# IMX6DL_POWER.net
KiCad netlist of a schematic drawn in Altium Designer
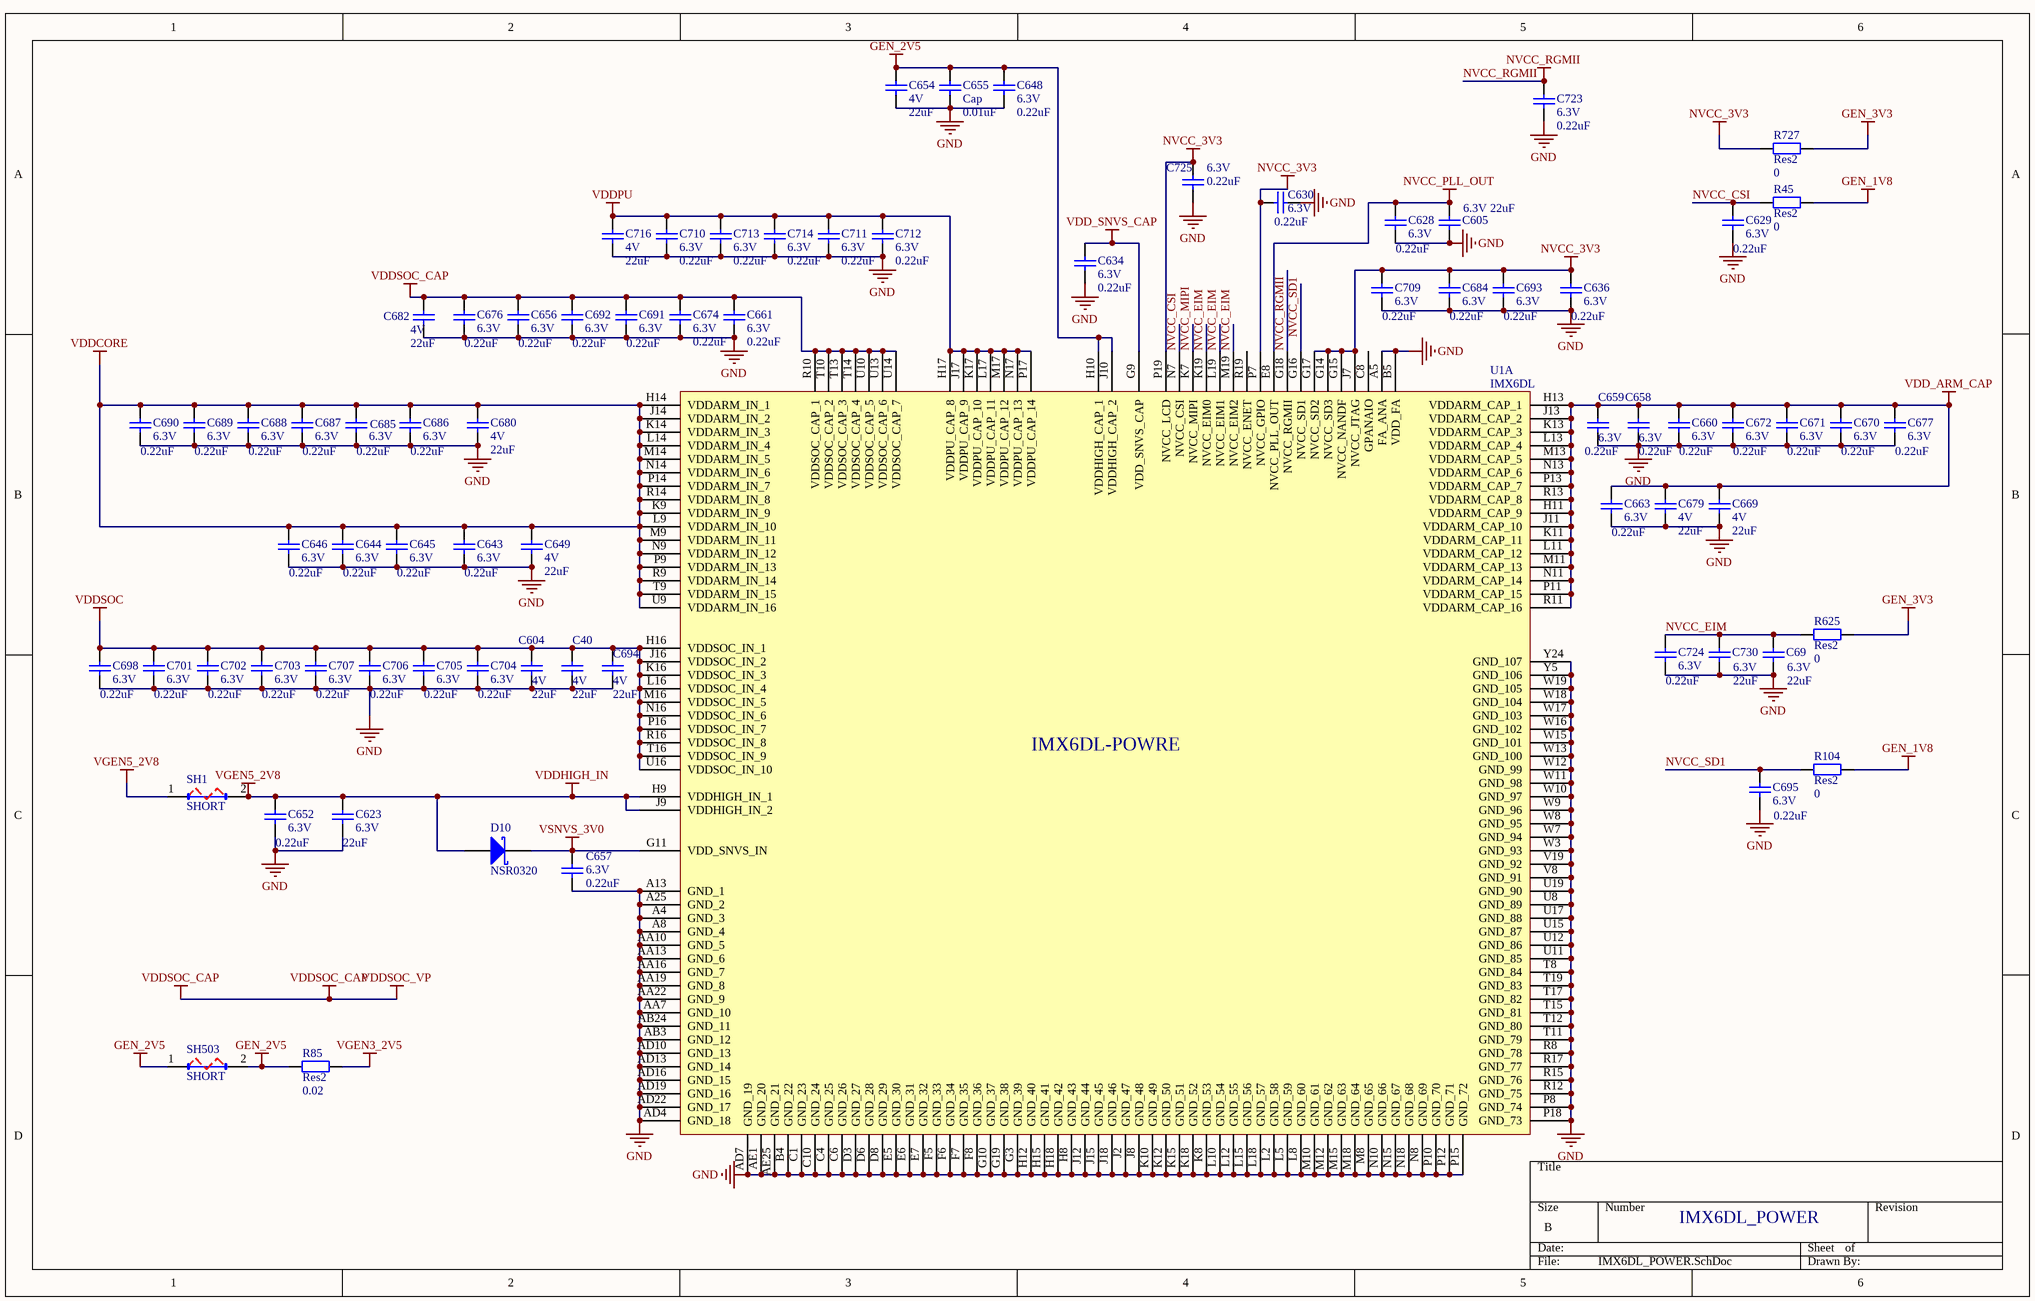
[diagram p0: IMX6DL_POWER.SchDoc]

(export (version "E")
  (design (tool "Eeschema 10.0.6"))
  (components
    (comp (ref "C40")
      (value "4V")
      (footprint "0603")
      (description "Capacitor")
      (fields (field (name "ALTIUM_VALUE") "22uF") (field (name "PUBLISHER") "Altium Limited"))
      (libsource (lib "Miscellaneous Devices") (part "Cap"))
    )
    (comp (ref "C69")
      (value "6.3V")
      (footprint "0603")
      (description "Capacitor")
      (fields (field (name "ALTIUM_VALUE") "22uF") (field (name "PUBLISHER") "Altium Limited"))
      (libsource (lib "Miscellaneous Devices") (part "Cap"))
    )
    (comp (ref "C604")
      (value "4V")
      (footprint "0603")
      (description "Capacitor")
      (fields (field (name "ALTIUM_VALUE") "22uF") (field (name "PUBLISHER") "Altium Limited"))
      (libsource (lib "Miscellaneous Devices") (part "Cap"))
    )
    (comp (ref "C605")
      (value "6.3V")
      (footprint "0603")
      (description "Capacitor")
      (fields (field (name "ALTIUM_VALUE") "22uF") (field (name "PUBLISHER") "Altium Limited"))
      (libsource (lib "Miscellaneous Devices") (part "Cap"))
    )
    (comp (ref "C623")
      (value "6.3V")
      (footprint "0603")
      (description "Capacitor")
      (fields (field (name "ALTIUM_VALUE") "22uF") (field (name "PUBLISHER") "Altium Limited"))
      (libsource (lib "Miscellaneous Devices") (part "Cap"))
    )
    (comp (ref "C628")
      (value "6.3V")
      (footprint "0201")
      (description "Capacitor")
      (fields (field (name "ALTIUM_VALUE") "0.22uF") (field (name "PUBLISHER") "Altium Limited"))
      (libsource (lib "Miscellaneous Devices") (part "Cap"))
    )
    (comp (ref "C629")
      (value "6.3V")
      (footprint "0201")
      (description "Capacitor")
      (fields (field (name "ALTIUM_VALUE") "0.22uF") (field (name "PUBLISHER") "Altium Limited"))
      (libsource (lib "Miscellaneous Devices") (part "Cap"))
    )
    (comp (ref "C630")
      (value "6.3V")
      (footprint "0201")
      (description "Capacitor")
      (fields (field (name "ALTIUM_VALUE") "0.22uF") (field (name "PUBLISHER") "Altium Limited"))
      (libsource (lib "Miscellaneous Devices") (part "Cap"))
    )
    (comp (ref "C634")
      (value "6.3V")
      (footprint "0201")
      (description "Capacitor")
      (fields (field (name "ALTIUM_VALUE") "0.22uF") (field (name "PUBLISHER") "Altium Limited"))
      (libsource (lib "Miscellaneous Devices") (part "Cap"))
    )
    (comp (ref "C636")
      (value "6.3V")
      (footprint "0201")
      (description "Capacitor")
      (fields (field (name "ALTIUM_VALUE") "0.22uF") (field (name "PUBLISHER") "Altium Limited"))
      (libsource (lib "Miscellaneous Devices") (part "Cap"))
    )
    (comp (ref "C643")
      (value "6.3V")
      (footprint "0201")
      (description "Capacitor")
      (fields (field (name "ALTIUM_VALUE") "0.22uF") (field (name "PUBLISHER") "Altium Limited"))
      (libsource (lib "Miscellaneous Devices") (part "Cap"))
    )
    (comp (ref "C644")
      (value "6.3V")
      (footprint "0201")
      (description "Capacitor")
      (fields (field (name "ALTIUM_VALUE") "0.22uF") (field (name "PUBLISHER") "Altium Limited"))
      (libsource (lib "Miscellaneous Devices") (part "Cap"))
    )
    (comp (ref "C645")
      (value "6.3V")
      (footprint "0201")
      (description "Capacitor")
      (fields (field (name "ALTIUM_VALUE") "0.22uF") (field (name "PUBLISHER") "Altium Limited"))
      (libsource (lib "Miscellaneous Devices") (part "Cap"))
    )
    (comp (ref "C646")
      (value "6.3V")
      (footprint "0201")
      (description "Capacitor")
      (fields (field (name "ALTIUM_VALUE") "0.22uF") (field (name "PUBLISHER") "Altium Limited"))
      (libsource (lib "Miscellaneous Devices") (part "Cap"))
    )
    (comp (ref "C648")
      (value "6.3V")
      (footprint "0201")
      (description "Capacitor")
      (fields (field (name "ALTIUM_VALUE") "0.22uF") (field (name "PUBLISHER") "Altium Limited"))
      (libsource (lib "Miscellaneous Devices") (part "Cap"))
    )
    (comp (ref "C649")
      (value "4V")
      (footprint "0603")
      (description "Capacitor")
      (fields (field (name "ALTIUM_VALUE") "22uF") (field (name "PUBLISHER") "Altium Limited"))
      (libsource (lib "Miscellaneous Devices") (part "Cap"))
    )
    (comp (ref "C652")
      (value "6.3V")
      (footprint "0201")
      (description "Capacitor")
      (fields (field (name "ALTIUM_VALUE") "0.22uF") (field (name "PUBLISHER") "Altium Limited"))
      (libsource (lib "Miscellaneous Devices") (part "Cap"))
    )
    (comp (ref "C654")
      (value "4V")
      (footprint "0603")
      (description "Capacitor")
      (fields (field (name "ALTIUM_VALUE") "22uF") (field (name "PUBLISHER") "Altium Limited"))
      (libsource (lib "Miscellaneous Devices") (part "Cap"))
    )
    (comp (ref "C655")
      (value "Cap")
      (footprint "0201")
      (description "Capacitor")
      (fields (field (name "ALTIUM_VALUE") "0.01uF") (field (name "PUBLISHER") "Altium Limited"))
      (libsource (lib "Miscellaneous Devices") (part "Cap"))
    )
    (comp (ref "C656")
      (value "6.3V")
      (footprint "0201")
      (description "Capacitor")
      (fields (field (name "ALTIUM_VALUE") "0.22uF") (field (name "PUBLISHER") "Altium Limited"))
      (libsource (lib "Miscellaneous Devices") (part "Cap"))
    )
    (comp (ref "C657")
      (value "6.3V")
      (footprint "0201")
      (description "Capacitor")
      (fields (field (name "ALTIUM_VALUE") "0.22uF") (field (name "PUBLISHER") "Altium Limited"))
      (libsource (lib "Miscellaneous Devices") (part "Cap"))
    )
    (comp (ref "C658")
      (value "6.3V")
      (footprint "0201")
      (description "Capacitor")
      (fields (field (name "ALTIUM_VALUE") "0.22uF") (field (name "PUBLISHER") "Altium Limited"))
      (libsource (lib "Miscellaneous Devices") (part "Cap"))
    )
    (comp (ref "C659")
      (value "6.3V")
      (footprint "0201")
      (description "Capacitor")
      (fields (field (name "ALTIUM_VALUE") "0.22uF") (field (name "PUBLISHER") "Altium Limited"))
      (libsource (lib "Miscellaneous Devices") (part "Cap"))
    )
    (comp (ref "C660")
      (value "6.3V")
      (footprint "0201")
      (description "Capacitor")
      (fields (field (name "ALTIUM_VALUE") "0.22uF") (field (name "PUBLISHER") "Altium Limited"))
      (libsource (lib "Miscellaneous Devices") (part "Cap"))
    )
    (comp (ref "C661")
      (value "6.3V")
      (footprint "0201")
      (description "Capacitor")
      (fields (field (name "ALTIUM_VALUE") "0.22uF") (field (name "PUBLISHER") "Altium Limited"))
      (libsource (lib "Miscellaneous Devices") (part "Cap"))
    )
    (comp (ref "C663")
      (value "6.3V")
      (footprint "0201")
      (description "Capacitor")
      (fields (field (name "ALTIUM_VALUE") "0.22uF") (field (name "PUBLISHER") "Altium Limited"))
      (libsource (lib "Miscellaneous Devices") (part "Cap"))
    )
    (comp (ref "C669")
      (value "4V")
      (footprint "0603")
      (description "Capacitor")
      (fields (field (name "ALTIUM_VALUE") "22uF") (field (name "PUBLISHER") "Altium Limited"))
      (libsource (lib "Miscellaneous Devices") (part "Cap"))
    )
    (comp (ref "C670")
      (value "6.3V")
      (footprint "0201")
      (description "Capacitor")
      (fields (field (name "ALTIUM_VALUE") "0.22uF") (field (name "PUBLISHER") "Altium Limited"))
      (libsource (lib "Miscellaneous Devices") (part "Cap"))
    )
    (comp (ref "C671")
      (value "6.3V")
      (footprint "0201")
      (description "Capacitor")
      (fields (field (name "ALTIUM_VALUE") "0.22uF") (field (name "PUBLISHER") "Altium Limited"))
      (libsource (lib "Miscellaneous Devices") (part "Cap"))
    )
    (comp (ref "C672")
      (value "6.3V")
      (footprint "0201")
      (description "Capacitor")
      (fields (field (name "ALTIUM_VALUE") "0.22uF") (field (name "PUBLISHER") "Altium Limited"))
      (libsource (lib "Miscellaneous Devices") (part "Cap"))
    )
    (comp (ref "C674")
      (value "6.3V")
      (footprint "0201")
      (description "Capacitor")
      (fields (field (name "ALTIUM_VALUE") "0.22uF") (field (name "PUBLISHER") "Altium Limited"))
      (libsource (lib "Miscellaneous Devices") (part "Cap"))
    )
    (comp (ref "C676")
      (value "6.3V")
      (footprint "0201")
      (description "Capacitor")
      (fields (field (name "ALTIUM_VALUE") "0.22uF") (field (name "PUBLISHER") "Altium Limited"))
      (libsource (lib "Miscellaneous Devices") (part "Cap"))
    )
    (comp (ref "C677")
      (value "6.3V")
      (footprint "0201")
      (description "Capacitor")
      (fields (field (name "ALTIUM_VALUE") "0.22uF") (field (name "PUBLISHER") "Altium Limited"))
      (libsource (lib "Miscellaneous Devices") (part "Cap"))
    )
    (comp (ref "C679")
      (value "4V")
      (footprint "0603")
      (description "Capacitor")
      (fields (field (name "ALTIUM_VALUE") "22uF") (field (name "PUBLISHER") "Altium Limited"))
      (libsource (lib "Miscellaneous Devices") (part "Cap"))
    )
    (comp (ref "C680")
      (value "4V")
      (footprint "0603")
      (description "Capacitor")
      (fields (field (name "ALTIUM_VALUE") "22uF") (field (name "PUBLISHER") "Altium Limited"))
      (libsource (lib "Miscellaneous Devices") (part "Cap"))
    )
    (comp (ref "C682")
      (value "4V")
      (footprint "0603")
      (description "Capacitor")
      (fields (field (name "ALTIUM_VALUE") "22uF") (field (name "PUBLISHER") "Altium Limited"))
      (libsource (lib "Miscellaneous Devices") (part "Cap"))
    )
    (comp (ref "C684")
      (value "6.3V")
      (footprint "0201")
      (description "Capacitor")
      (fields (field (name "ALTIUM_VALUE") "0.22uF") (field (name "PUBLISHER") "Altium Limited"))
      (libsource (lib "Miscellaneous Devices") (part "Cap"))
    )
    (comp (ref "C685")
      (value "6.3V")
      (footprint "0201")
      (description "Capacitor")
      (fields (field (name "ALTIUM_VALUE") "0.22uF") (field (name "PUBLISHER") "Altium Limited"))
      (libsource (lib "Miscellaneous Devices") (part "Cap"))
    )
    (comp (ref "C686")
      (value "6.3V")
      (footprint "0201")
      (description "Capacitor")
      (fields (field (name "ALTIUM_VALUE") "0.22uF") (field (name "PUBLISHER") "Altium Limited"))
      (libsource (lib "Miscellaneous Devices") (part "Cap"))
    )
    (comp (ref "C687")
      (value "6.3V")
      (footprint "0201")
      (description "Capacitor")
      (fields (field (name "ALTIUM_VALUE") "0.22uF") (field (name "PUBLISHER") "Altium Limited"))
      (libsource (lib "Miscellaneous Devices") (part "Cap"))
    )
    (comp (ref "C688")
      (value "6.3V")
      (footprint "0201")
      (description "Capacitor")
      (fields (field (name "ALTIUM_VALUE") "0.22uF") (field (name "PUBLISHER") "Altium Limited"))
      (libsource (lib "Miscellaneous Devices") (part "Cap"))
    )
    (comp (ref "C689")
      (value "6.3V")
      (footprint "0201")
      (description "Capacitor")
      (fields (field (name "ALTIUM_VALUE") "0.22uF") (field (name "PUBLISHER") "Altium Limited"))
      (libsource (lib "Miscellaneous Devices") (part "Cap"))
    )
    (comp (ref "C690")
      (value "6.3V")
      (footprint "0201")
      (description "Capacitor")
      (fields (field (name "ALTIUM_VALUE") "0.22uF") (field (name "PUBLISHER") "Altium Limited"))
      (libsource (lib "Miscellaneous Devices") (part "Cap"))
    )
    (comp (ref "C691")
      (value "6.3V")
      (footprint "0201")
      (description "Capacitor")
      (fields (field (name "ALTIUM_VALUE") "0.22uF") (field (name "PUBLISHER") "Altium Limited"))
      (libsource (lib "Miscellaneous Devices") (part "Cap"))
    )
    (comp (ref "C692")
      (value "6.3V")
      (footprint "0201")
      (description "Capacitor")
      (fields (field (name "ALTIUM_VALUE") "0.22uF") (field (name "PUBLISHER") "Altium Limited"))
      (libsource (lib "Miscellaneous Devices") (part "Cap"))
    )
    (comp (ref "C693")
      (value "6.3V")
      (footprint "0201")
      (description "Capacitor")
      (fields (field (name "ALTIUM_VALUE") "0.22uF") (field (name "PUBLISHER") "Altium Limited"))
      (libsource (lib "Miscellaneous Devices") (part "Cap"))
    )
    (comp (ref "C694")
      (value "4V")
      (footprint "0603")
      (description "Capacitor")
      (fields (field (name "ALTIUM_VALUE") "22uF") (field (name "PUBLISHER") "Altium Limited"))
      (libsource (lib "Miscellaneous Devices") (part "Cap"))
    )
    (comp (ref "C695")
      (value "6.3V")
      (footprint "0201")
      (description "Capacitor")
      (fields (field (name "ALTIUM_VALUE") "0.22uF") (field (name "PUBLISHER") "Altium Limited"))
      (libsource (lib "Miscellaneous Devices") (part "Cap"))
    )
    (comp (ref "C698")
      (value "6.3V")
      (footprint "0201")
      (description "Capacitor")
      (fields (field (name "ALTIUM_VALUE") "0.22uF") (field (name "PUBLISHER") "Altium Limited"))
      (libsource (lib "Miscellaneous Devices") (part "Cap"))
    )
    (comp (ref "C701")
      (value "6.3V")
      (footprint "0201")
      (description "Capacitor")
      (fields (field (name "ALTIUM_VALUE") "0.22uF") (field (name "PUBLISHER") "Altium Limited"))
      (libsource (lib "Miscellaneous Devices") (part "Cap"))
    )
    (comp (ref "C702")
      (value "6.3V")
      (footprint "0201")
      (description "Capacitor")
      (fields (field (name "ALTIUM_VALUE") "0.22uF") (field (name "PUBLISHER") "Altium Limited"))
      (libsource (lib "Miscellaneous Devices") (part "Cap"))
    )
    (comp (ref "C703")
      (value "6.3V")
      (footprint "0201")
      (description "Capacitor")
      (fields (field (name "ALTIUM_VALUE") "0.22uF") (field (name "PUBLISHER") "Altium Limited"))
      (libsource (lib "Miscellaneous Devices") (part "Cap"))
    )
    (comp (ref "C704")
      (value "6.3V")
      (footprint "0201")
      (description "Capacitor")
      (fields (field (name "ALTIUM_VALUE") "0.22uF") (field (name "PUBLISHER") "Altium Limited"))
      (libsource (lib "Miscellaneous Devices") (part "Cap"))
    )
    (comp (ref "C705")
      (value "6.3V")
      (footprint "0201")
      (description "Capacitor")
      (fields (field (name "ALTIUM_VALUE") "0.22uF") (field (name "PUBLISHER") "Altium Limited"))
      (libsource (lib "Miscellaneous Devices") (part "Cap"))
    )
    (comp (ref "C706")
      (value "6.3V")
      (footprint "0201")
      (description "Capacitor")
      (fields (field (name "ALTIUM_VALUE") "0.22uF") (field (name "PUBLISHER") "Altium Limited"))
      (libsource (lib "Miscellaneous Devices") (part "Cap"))
    )
    (comp (ref "C707")
      (value "6.3V")
      (footprint "0201")
      (description "Capacitor")
      (fields (field (name "ALTIUM_VALUE") "0.22uF") (field (name "PUBLISHER") "Altium Limited"))
      (libsource (lib "Miscellaneous Devices") (part "Cap"))
    )
    (comp (ref "C709")
      (value "6.3V")
      (footprint "0201")
      (description "Capacitor")
      (fields (field (name "ALTIUM_VALUE") "0.22uF") (field (name "PUBLISHER") "Altium Limited"))
      (libsource (lib "Miscellaneous Devices") (part "Cap"))
    )
    (comp (ref "C710")
      (value "6.3V")
      (footprint "0201")
      (description "Capacitor")
      (fields (field (name "ALTIUM_VALUE") "0.22uF") (field (name "PUBLISHER") "Altium Limited"))
      (libsource (lib "Miscellaneous Devices") (part "Cap"))
    )
    (comp (ref "C711")
      (value "6.3V")
      (footprint "0201")
      (description "Capacitor")
      (fields (field (name "ALTIUM_VALUE") "0.22uF") (field (name "PUBLISHER") "Altium Limited"))
      (libsource (lib "Miscellaneous Devices") (part "Cap"))
    )
    (comp (ref "C712")
      (value "6.3V")
      (footprint "0201")
      (description "Capacitor")
      (fields (field (name "ALTIUM_VALUE") "0.22uF") (field (name "PUBLISHER") "Altium Limited"))
      (libsource (lib "Miscellaneous Devices") (part "Cap"))
    )
    (comp (ref "C713")
      (value "6.3V")
      (footprint "0201")
      (description "Capacitor")
      (fields (field (name "ALTIUM_VALUE") "0.22uF") (field (name "PUBLISHER") "Altium Limited"))
      (libsource (lib "Miscellaneous Devices") (part "Cap"))
    )
    (comp (ref "C714")
      (value "6.3V")
      (footprint "0201")
      (description "Capacitor")
      (fields (field (name "ALTIUM_VALUE") "0.22uF") (field (name "PUBLISHER") "Altium Limited"))
      (libsource (lib "Miscellaneous Devices") (part "Cap"))
    )
    (comp (ref "C716")
      (value "4V")
      (footprint "0603")
      (description "Capacitor")
      (fields (field (name "ALTIUM_VALUE") "22uF") (field (name "PUBLISHER") "Altium Limited"))
      (libsource (lib "Miscellaneous Devices") (part "Cap"))
    )
    (comp (ref "C723")
      (value "6.3V")
      (footprint "0201")
      (description "Capacitor")
      (fields (field (name "ALTIUM_VALUE") "0.22uF") (field (name "PUBLISHER") "Altium Limited"))
      (libsource (lib "Miscellaneous Devices") (part "Cap"))
    )
    (comp (ref "C724")
      (value "6.3V")
      (footprint "0201")
      (description "Capacitor")
      (fields (field (name "ALTIUM_VALUE") "0.22uF") (field (name "PUBLISHER") "Altium Limited"))
      (libsource (lib "Miscellaneous Devices") (part "Cap"))
    )
    (comp (ref "C725")
      (value "6.3V")
      (footprint "0201")
      (description "Capacitor")
      (fields (field (name "ALTIUM_VALUE") "0.22uF") (field (name "PUBLISHER") "Altium Limited"))
      (libsource (lib "Miscellaneous Devices") (part "Cap"))
    )
    (comp (ref "C730")
      (value "6.3V")
      (footprint "0603")
      (description "Capacitor")
      (fields (field (name "ALTIUM_VALUE") "22uF") (field (name "PUBLISHER") "Altium Limited"))
      (libsource (lib "Miscellaneous Devices") (part "Cap"))
    )
    (comp (ref "D10")
      (value "NSR0320")
      (footprint "NSR0320MW2T1G-SOD323")
      (libsource (lib "IMX6DL") (part "NSR0320"))
    )
    (comp (ref "R45")
      (value "Res2")
      (footprint "0402")
      (description "Resistor")
      (fields (field (name "ALTIUM_VALUE") "0") (field (name "PUBLISHER") "Altium Limited"))
      (libsource (lib "Miscellaneous Devices") (part "Res2"))
    )
    (comp (ref "R85")
      (value "Res2")
      (footprint "0805")
      (description "Resistor")
      (fields (field (name "ALTIUM_VALUE") "0.02") (field (name "PUBLISHER") "Altium Limited"))
      (libsource (lib "Miscellaneous Devices") (part "Res2"))
    )
    (comp (ref "R104")
      (value "Res2")
      (footprint "0402")
      (description "Resistor")
      (fields (field (name "ALTIUM_VALUE") "0") (field (name "PUBLISHER") "Altium Limited"))
      (libsource (lib "Miscellaneous Devices") (part "Res2"))
    )
    (comp (ref "R625")
      (value "Res2")
      (footprint "0402")
      (description "Resistor")
      (fields (field (name "ALTIUM_VALUE") "0") (field (name "PUBLISHER") "Altium Limited"))
      (libsource (lib "Miscellaneous Devices") (part "Res2"))
    )
    (comp (ref "R727")
      (value "Res2")
      (footprint "0402")
      (description "Resistor")
      (fields (field (name "ALTIUM_VALUE") "0") (field (name "PUBLISHER") "Altium Limited"))
      (libsource (lib "Miscellaneous Devices") (part "Res2"))
    )
    (comp (ref "SH1") (value "SHORT") (footprint "SHORT_SH") (libsource (lib "IMX6DL") (part "SOLDER SHORT")))
    (comp (ref "SH503")
      (value "SHORT")
      (footprint "SHORT_SH")
      (libsource (lib "IMX6DL") (part "SOLDER SHORT"))
    )
    (comp (ref "U1")
      (value "IMX6DL")
      (footprint "IMX6DL-BGA624x25")
      (libsource (lib "IMX6DL") (part "IMX6DL"))
    )
  )
  (nets
    (net (code "1") (name "/NVCC_CSI") (class "Default")
      (node (ref "C629") (pin "2") (pinfunction "2_2") (pintype "passive"))
      (node (ref "R45") (pin "1") (pinfunction "1_1") (pintype "passive"))
      (node (ref "U1") (pin "N7") (pinfunction "NVCC_CSI_N7") (pintype "passive"))
    )
    (net (code "2") (name "/NVCC_EIM") (class "Default")
      (node (ref "C69") (pin "1") (pinfunction "1_1") (pintype "passive"))
      (node (ref "C724") (pin "2") (pinfunction "2_2") (pintype "passive"))
      (node (ref "C730") (pin "1") (pinfunction "1_1") (pintype "passive"))
      (node (ref "R625") (pin "1") (pinfunction "1_1") (pintype "passive"))
      (node (ref "U1") (pin "K19") (pinfunction "NVCC_EIM0_K19") (pintype "passive"))
      (node (ref "U1") (pin "L19") (pinfunction "NVCC_EIM1_L19") (pintype "passive"))
      (node (ref "U1") (pin "M19") (pinfunction "NVCC_EIM2_M19") (pintype "passive"))
    )
    (net (code "3") (name "/NVCC_MIPI") (class "Default")
      (node (ref "U1") (pin "K7") (pinfunction "NVCC_MIPI_K7") (pintype "passive"))
    )
    (net (code "4") (name "/NVCC_SD1") (class "Default")
      (node (ref "C695") (pin "2") (pinfunction "2_2") (pintype "passive"))
      (node (ref "R104") (pin "1") (pinfunction "1_1") (pintype "passive"))
      (node (ref "U1") (pin "G16") (pinfunction "NVCC_SD1_G16") (pintype "passive"))
    )
    (net (code "5") (name "GEN_1V8") (class "Default")
      (node (ref "R104") (pin "2") (pinfunction "2_2") (pintype "passive"))
      (node (ref "R45") (pin "2") (pinfunction "2_2") (pintype "passive"))
    )
    (net (code "6") (name "GEN_2V5") (class "Default")
      (node (ref "C648") (pin "2") (pinfunction "2_2") (pintype "passive"))
      (node (ref "C654") (pin "1") (pinfunction "1_1") (pintype "passive"))
      (node (ref "C655") (pin "2") (pinfunction "2_2") (pintype "passive"))
      (node (ref "R85") (pin "1") (pinfunction "1_1") (pintype "passive"))
      (node (ref "SH503") (pin "1") (pinfunction "VCCIO_1") (pintype "passive"))
      (node (ref "SH503") (pin "2") (pinfunction "VCCIO_2") (pintype "passive"))
      (node (ref "U1") (pin "H10") (pinfunction "VDDHIGH_CAP_1_H10") (pintype "passive"))
      (node (ref "U1") (pin "J10") (pinfunction "VDDHIGH_CAP_2_J10") (pintype "passive"))
    )
    (net (code "7") (name "GEN_3V3") (class "Default")
      (node (ref "R625") (pin "2") (pinfunction "2_2") (pintype "passive"))
      (node (ref "R727") (pin "2") (pinfunction "2_2") (pintype "passive"))
    )
    (net (code "8") (name "GND") (class "Default")
      (node (ref "C40") (pin "1") (pinfunction "1_1") (pintype "passive"))
      (node (ref "C604") (pin "1") (pinfunction "1_1") (pintype "passive"))
      (node (ref "C605") (pin "2") (pinfunction "2_2") (pintype "passive"))
      (node (ref "C623") (pin "1") (pinfunction "1_1") (pintype "passive"))
      (node (ref "C628") (pin "1") (pinfunction "1_1") (pintype "passive"))
      (node (ref "C629") (pin "1") (pinfunction "1_1") (pintype "passive"))
      (node (ref "C630") (pin "2") (pinfunction "2_2") (pintype "passive"))
      (node (ref "C634") (pin "2") (pinfunction "2_2") (pintype "passive"))
      (node (ref "C636") (pin "1") (pinfunction "1_1") (pintype "passive"))
      (node (ref "C643") (pin "1") (pinfunction "1_1") (pintype "passive"))
      (node (ref "C644") (pin "1") (pinfunction "1_1") (pintype "passive"))
      (node (ref "C645") (pin "1") (pinfunction "1_1") (pintype "passive"))
      (node (ref "C646") (pin "1") (pinfunction "1_1") (pintype "passive"))
      (node (ref "C648") (pin "1") (pinfunction "1_1") (pintype "passive"))
      (node (ref "C649") (pin "1") (pinfunction "1_1") (pintype "passive"))
      (node (ref "C652") (pin "1") (pinfunction "1_1") (pintype "passive"))
      (node (ref "C654") (pin "2") (pinfunction "2_2") (pintype "passive"))
      (node (ref "C655") (pin "1") (pinfunction "1_1") (pintype "passive"))
      (node (ref "C656") (pin "1") (pinfunction "1_1") (pintype "passive"))
      (node (ref "C657") (pin "1") (pinfunction "1_1") (pintype "passive"))
      (node (ref "C658") (pin "1") (pinfunction "1_1") (pintype "passive"))
      (node (ref "C659") (pin "1") (pinfunction "1_1") (pintype "passive"))
      (node (ref "C660") (pin "1") (pinfunction "1_1") (pintype "passive"))
      (node (ref "C661") (pin "1") (pinfunction "1_1") (pintype "passive"))
      (node (ref "C663") (pin "1") (pinfunction "1_1") (pintype "passive"))
      (node (ref "C669") (pin "1") (pinfunction "1_1") (pintype "passive"))
      (node (ref "C670") (pin "1") (pinfunction "1_1") (pintype "passive"))
      (node (ref "C671") (pin "1") (pinfunction "1_1") (pintype "passive"))
      (node (ref "C672") (pin "1") (pinfunction "1_1") (pintype "passive"))
      (node (ref "C674") (pin "1") (pinfunction "1_1") (pintype "passive"))
      (node (ref "C676") (pin "1") (pinfunction "1_1") (pintype "passive"))
      (node (ref "C677") (pin "1") (pinfunction "1_1") (pintype "passive"))
      (node (ref "C679") (pin "1") (pinfunction "1_1") (pintype "passive"))
      (node (ref "C680") (pin "1") (pinfunction "1_1") (pintype "passive"))
      (node (ref "C682") (pin "1") (pinfunction "1_1") (pintype "passive"))
      (node (ref "C684") (pin "1") (pinfunction "1_1") (pintype "passive"))
      (node (ref "C685") (pin "1") (pinfunction "1_1") (pintype "passive"))
      (node (ref "C686") (pin "1") (pinfunction "1_1") (pintype "passive"))
      (node (ref "C687") (pin "1") (pinfunction "1_1") (pintype "passive"))
      (node (ref "C688") (pin "1") (pinfunction "1_1") (pintype "passive"))
      (node (ref "C689") (pin "1") (pinfunction "1_1") (pintype "passive"))
      (node (ref "C69") (pin "2") (pinfunction "2_2") (pintype "passive"))
      (node (ref "C690") (pin "1") (pinfunction "1_1") (pintype "passive"))
      (node (ref "C691") (pin "1") (pinfunction "1_1") (pintype "passive"))
      (node (ref "C692") (pin "1") (pinfunction "1_1") (pintype "passive"))
      (node (ref "C693") (pin "1") (pinfunction "1_1") (pintype "passive"))
      (node (ref "C694") (pin "1") (pinfunction "1_1") (pintype "passive"))
      (node (ref "C695") (pin "1") (pinfunction "1_1") (pintype "passive"))
      (node (ref "C698") (pin "1") (pinfunction "1_1") (pintype "passive"))
      (node (ref "C701") (pin "1") (pinfunction "1_1") (pintype "passive"))
      (node (ref "C702") (pin "1") (pinfunction "1_1") (pintype "passive"))
      (node (ref "C703") (pin "1") (pinfunction "1_1") (pintype "passive"))
      (node (ref "C704") (pin "1") (pinfunction "1_1") (pintype "passive"))
      (node (ref "C705") (pin "1") (pinfunction "1_1") (pintype "passive"))
      (node (ref "C706") (pin "1") (pinfunction "1_1") (pintype "passive"))
      (node (ref "C707") (pin "1") (pinfunction "1_1") (pintype "passive"))
      (node (ref "C709") (pin "1") (pinfunction "1_1") (pintype "passive"))
      (node (ref "C710") (pin "1") (pinfunction "1_1") (pintype "passive"))
      (node (ref "C711") (pin "1") (pinfunction "1_1") (pintype "passive"))
      (node (ref "C712") (pin "1") (pinfunction "1_1") (pintype "passive"))
      (node (ref "C713") (pin "1") (pinfunction "1_1") (pintype "passive"))
      (node (ref "C714") (pin "1") (pinfunction "1_1") (pintype "passive"))
      (node (ref "C716") (pin "1") (pinfunction "1_1") (pintype "passive"))
      (node (ref "C723") (pin "2") (pinfunction "2_2") (pintype "passive"))
      (node (ref "C724") (pin "1") (pinfunction "1_1") (pintype "passive"))
      (node (ref "C725") (pin "2") (pinfunction "2_2") (pintype "passive"))
      (node (ref "C730") (pin "2") (pinfunction "2_2") (pintype "passive"))
      (node (ref "U1") (pin "A13") (pinfunction "GND_1_A13") (pintype "passive"))
      (node (ref "U1") (pin "A25") (pinfunction "GND_2_A25") (pintype "passive"))
      (node (ref "U1") (pin "A4") (pinfunction "GND_3_A4") (pintype "passive"))
      (node (ref "U1") (pin "A5") (pinfunction "FA_ANA_A5") (pintype "passive"))
      (node (ref "U1") (pin "A8") (pinfunction "GND_4_A8") (pintype "passive"))
      (node (ref "U1") (pin "AA10") (pinfunction "GND_5_AA10") (pintype "passive"))
      (node (ref "U1") (pin "AA13") (pinfunction "GND_6_AA13") (pintype "passive"))
      (node (ref "U1") (pin "AA16") (pinfunction "GND_7_AA16") (pintype "passive"))
      (node (ref "U1") (pin "AA19") (pinfunction "GND_8_AA19") (pintype "passive"))
      (node (ref "U1") (pin "AA22") (pinfunction "GND_9_AA22") (pintype "passive"))
      (node (ref "U1") (pin "AA7") (pinfunction "GND_10_AA7") (pintype "passive"))
      (node (ref "U1") (pin "AB24") (pinfunction "GND_11_AB24") (pintype "passive"))
      (node (ref "U1") (pin "AB3") (pinfunction "GND_12_AB3") (pintype "passive"))
      (node (ref "U1") (pin "AD10") (pinfunction "GND_13_AD10") (pintype "passive"))
      (node (ref "U1") (pin "AD13") (pinfunction "GND_14_AD13") (pintype "passive"))
      (node (ref "U1") (pin "AD16") (pinfunction "GND_15_AD16") (pintype "passive"))
      (node (ref "U1") (pin "AD19") (pinfunction "GND_16_AD19") (pintype "passive"))
      (node (ref "U1") (pin "AD22") (pinfunction "GND_17_AD22") (pintype "passive"))
      (node (ref "U1") (pin "AD4") (pinfunction "GND_18_AD4") (pintype "passive"))
      (node (ref "U1") (pin "AD7") (pinfunction "GND_19_AD7") (pintype "passive"))
      (node (ref "U1") (pin "AE1") (pinfunction "GND_20_AE1") (pintype "passive"))
      (node (ref "U1") (pin "AE25") (pinfunction "GND_21_AE25") (pintype "passive"))
      (node (ref "U1") (pin "B4") (pinfunction "GND_22_B4") (pintype "passive"))
      (node (ref "U1") (pin "B5") (pinfunction "VDD_FA_B5") (pintype "passive"))
      (node (ref "U1") (pin "C1") (pinfunction "GND_23_C1") (pintype "passive"))
      (node (ref "U1") (pin "C10") (pinfunction "GND_24_C10") (pintype "passive"))
      (node (ref "U1") (pin "C4") (pinfunction "GND_25_C4") (pintype "passive"))
      (node (ref "U1") (pin "C6") (pinfunction "GND_26_C6") (pintype "passive"))
      (node (ref "U1") (pin "D3") (pinfunction "GND_27_D3") (pintype "passive"))
      (node (ref "U1") (pin "D6") (pinfunction "GND_28_D6") (pintype "passive"))
      (node (ref "U1") (pin "D8") (pinfunction "GND_29_D8") (pintype "passive"))
      (node (ref "U1") (pin "E5") (pinfunction "GND_30_E5") (pintype "passive"))
      (node (ref "U1") (pin "E6") (pinfunction "GND_31_E6") (pintype "passive"))
      (node (ref "U1") (pin "E7") (pinfunction "GND_32_E7") (pintype "passive"))
      (node (ref "U1") (pin "F5") (pinfunction "GND_33_F5") (pintype "passive"))
      (node (ref "U1") (pin "F6") (pinfunction "GND_34_F6") (pintype "passive"))
      (node (ref "U1") (pin "F7") (pinfunction "GND_35_F7") (pintype "passive"))
      (node (ref "U1") (pin "F8") (pinfunction "GND_36_F8") (pintype "passive"))
      (node (ref "U1") (pin "G10") (pinfunction "GND_37_G10") (pintype "passive"))
      (node (ref "U1") (pin "G19") (pinfunction "GND_38_G19") (pintype "passive"))
      (node (ref "U1") (pin "G3") (pinfunction "GND_39_G3") (pintype "passive"))
      (node (ref "U1") (pin "H12") (pinfunction "GND_40_H12") (pintype "passive"))
      (node (ref "U1") (pin "H15") (pinfunction "GND_41_H15") (pintype "passive"))
      (node (ref "U1") (pin "H18") (pinfunction "GND_42_H18") (pintype "passive"))
      (node (ref "U1") (pin "H8") (pinfunction "GND_43_H8") (pintype "passive"))
      (node (ref "U1") (pin "J12") (pinfunction "GND_44_J12") (pintype "passive"))
      (node (ref "U1") (pin "J15") (pinfunction "GND_45_J15") (pintype "passive"))
      (node (ref "U1") (pin "J18") (pinfunction "GND_46_J18") (pintype "passive"))
      (node (ref "U1") (pin "J2") (pinfunction "GND_47_J2") (pintype "passive"))
      (node (ref "U1") (pin "J8") (pinfunction "GND_48_J8") (pintype "passive"))
      (node (ref "U1") (pin "K10") (pinfunction "GND_49_K10") (pintype "passive"))
      (node (ref "U1") (pin "K12") (pinfunction "GND_50_K12") (pintype "passive"))
      (node (ref "U1") (pin "K15") (pinfunction "GND_51_K15") (pintype "passive"))
      (node (ref "U1") (pin "K18") (pinfunction "GND_52_K18") (pintype "passive"))
      (node (ref "U1") (pin "K8") (pinfunction "GND_53_K8") (pintype "passive"))
      (node (ref "U1") (pin "L10") (pinfunction "GND_54_L10") (pintype "passive"))
      (node (ref "U1") (pin "L12") (pinfunction "GND_55_L12") (pintype "passive"))
      (node (ref "U1") (pin "L15") (pinfunction "GND_56_L15") (pintype "passive"))
      (node (ref "U1") (pin "L18") (pinfunction "GND_57_L18") (pintype "passive"))
      (node (ref "U1") (pin "L2") (pinfunction "GND_58_L2") (pintype "passive"))
      (node (ref "U1") (pin "L5") (pinfunction "GND_59_L5") (pintype "passive"))
      (node (ref "U1") (pin "L8") (pinfunction "GND_60_L8") (pintype "passive"))
      (node (ref "U1") (pin "M10") (pinfunction "GND_61_M10") (pintype "passive"))
      (node (ref "U1") (pin "M12") (pinfunction "GND_62_M12") (pintype "passive"))
      (node (ref "U1") (pin "M15") (pinfunction "GND_63_M15") (pintype "passive"))
      (node (ref "U1") (pin "M18") (pinfunction "GND_64_M18") (pintype "passive"))
      (node (ref "U1") (pin "M8") (pinfunction "GND_65_M8") (pintype "passive"))
      (node (ref "U1") (pin "N10") (pinfunction "GND_66_N10") (pintype "passive"))
      (node (ref "U1") (pin "N15") (pinfunction "GND_67_N15") (pintype "passive"))
      (node (ref "U1") (pin "N18") (pinfunction "GND_68_N18") (pintype "passive"))
      (node (ref "U1") (pin "N8") (pinfunction "GND_69_N8") (pintype "passive"))
      (node (ref "U1") (pin "P10") (pinfunction "GND_70_P10") (pintype "passive"))
      (node (ref "U1") (pin "P12") (pinfunction "GND_71_P12") (pintype "passive"))
      (node (ref "U1") (pin "P15") (pinfunction "GND_72_P15") (pintype "passive"))
      (node (ref "U1") (pin "P18") (pinfunction "GND_73_P18") (pintype "passive"))
      (node (ref "U1") (pin "P8") (pinfunction "GND_74_P8") (pintype "passive"))
      (node (ref "U1") (pin "R12") (pinfunction "GND_75_R12") (pintype "passive"))
      (node (ref "U1") (pin "R15") (pinfunction "GND_76_R15") (pintype "passive"))
      (node (ref "U1") (pin "R17") (pinfunction "GND_77_R17") (pintype "passive"))
      (node (ref "U1") (pin "R8") (pinfunction "GND_78_R8") (pintype "passive"))
      (node (ref "U1") (pin "T11") (pinfunction "GND_79_T11") (pintype "passive"))
      (node (ref "U1") (pin "T12") (pinfunction "GND_80_T12") (pintype "passive"))
      (node (ref "U1") (pin "T15") (pinfunction "GND_81_T15") (pintype "passive"))
      (node (ref "U1") (pin "T17") (pinfunction "GND_82_T17") (pintype "passive"))
      (node (ref "U1") (pin "T19") (pinfunction "GND_83_T19") (pintype "passive"))
      (node (ref "U1") (pin "T8") (pinfunction "GND_84_T8") (pintype "passive"))
      (node (ref "U1") (pin "U11") (pinfunction "GND_85_U11") (pintype "passive"))
      (node (ref "U1") (pin "U12") (pinfunction "GND_86_U12") (pintype "passive"))
      (node (ref "U1") (pin "U15") (pinfunction "GND_87_U15") (pintype "passive"))
      (node (ref "U1") (pin "U17") (pinfunction "GND_88_U17") (pintype "passive"))
      (node (ref "U1") (pin "U19") (pinfunction "GND_90_U19") (pintype "passive"))
      (node (ref "U1") (pin "U8") (pinfunction "GND_89_U8") (pintype "passive"))
      (node (ref "U1") (pin "V19") (pinfunction "GND_92_V19") (pintype "passive"))
      (node (ref "U1") (pin "V8") (pinfunction "GND_91_V8") (pintype "passive"))
      (node (ref "U1") (pin "W10") (pinfunction "GND_97_W10") (pintype "passive"))
      (node (ref "U1") (pin "W11") (pinfunction "GND_98_W11") (pintype "passive"))
      (node (ref "U1") (pin "W12") (pinfunction "GND_99_W12") (pintype "passive"))
      (node (ref "U1") (pin "W13") (pinfunction "GND_100_W13") (pintype "passive"))
      (node (ref "U1") (pin "W15") (pinfunction "GND_101_W15") (pintype "passive"))
      (node (ref "U1") (pin "W16") (pinfunction "GND_102_W16") (pintype "passive"))
      (node (ref "U1") (pin "W17") (pinfunction "GND_103_W17") (pintype "passive"))
      (node (ref "U1") (pin "W18") (pinfunction "GND_104_W18") (pintype "passive"))
      (node (ref "U1") (pin "W19") (pinfunction "GND_105_W19") (pintype "passive"))
      (node (ref "U1") (pin "W3") (pinfunction "GND_93_W3") (pintype "passive"))
      (node (ref "U1") (pin "W7") (pinfunction "GND_94_W7") (pintype "passive"))
      (node (ref "U1") (pin "W8") (pinfunction "GND_95_W8") (pintype "passive"))
      (node (ref "U1") (pin "W9") (pinfunction "GND_96_W9") (pintype "passive"))
      (node (ref "U1") (pin "Y24") (pinfunction "GND_107_Y24") (pintype "passive"))
      (node (ref "U1") (pin "Y5") (pinfunction "GND_106_Y5") (pintype "passive"))
    )
    (net (code "9") (name "NVCC_3V3") (class "Default")
      (node (ref "C630") (pin "1") (pinfunction "1_1") (pintype "passive"))
      (node (ref "C636") (pin "2") (pinfunction "2_2") (pintype "passive"))
      (node (ref "C684") (pin "2") (pinfunction "2_2") (pintype "passive"))
      (node (ref "C693") (pin "2") (pinfunction "2_2") (pintype "passive"))
      (node (ref "C709") (pin "2") (pinfunction "2_2") (pintype "passive"))
      (node (ref "C725") (pin "1") (pinfunction "1_1") (pintype "passive"))
      (node (ref "R727") (pin "1") (pinfunction "1_1") (pintype "passive"))
      (node (ref "U1") (pin "G14") (pinfunction "NVCC_SD3_G14") (pintype "passive"))
      (node (ref "U1") (pin "G15") (pinfunction "NVCC_NANDF_G15") (pintype "passive"))
      (node (ref "U1") (pin "G17") (pinfunction "NVCC_SD2_G17") (pintype "passive"))
      (node (ref "U1") (pin "J7") (pinfunction "NVCC_JTAG_J7") (pintype "passive"))
      (node (ref "U1") (pin "P19") (pinfunction "NVCC_LCD_P19") (pintype "passive"))
      (node (ref "U1") (pin "P7") (pinfunction "NVCC_GPIO_P7") (pintype "passive"))
    )
    (net (code "10") (name "NVCC_PLL_OUT") (class "Default")
      (node (ref "C605") (pin "1") (pinfunction "1_1") (pintype "passive"))
      (node (ref "C628") (pin "2") (pinfunction "2_2") (pintype "passive"))
      (node (ref "U1") (pin "E8") (pinfunction "NVCC_PLL_OUT_E8") (pintype "passive"))
    )
    (net (code "11") (name "NVCC_RGMII") (class "Default")
      (node (ref "C723") (pin "1") (pinfunction "1_1") (pintype "passive"))
      (node (ref "U1") (pin "G18") (pinfunction "NVCC_RGMII_G18") (pintype "passive"))
    )
    (net (code "12") (name "VDDCORE") (class "Default")
      (node (ref "C643") (pin "2") (pinfunction "2_2") (pintype "passive"))
      (node (ref "C644") (pin "2") (pinfunction "2_2") (pintype "passive"))
      (node (ref "C645") (pin "2") (pinfunction "2_2") (pintype "passive"))
      (node (ref "C646") (pin "2") (pinfunction "2_2") (pintype "passive"))
      (node (ref "C649") (pin "2") (pinfunction "2_2") (pintype "passive"))
      (node (ref "C680") (pin "2") (pinfunction "2_2") (pintype "passive"))
      (node (ref "C685") (pin "2") (pinfunction "2_2") (pintype "passive"))
      (node (ref "C686") (pin "2") (pinfunction "2_2") (pintype "passive"))
      (node (ref "C687") (pin "2") (pinfunction "2_2") (pintype "passive"))
      (node (ref "C688") (pin "2") (pinfunction "2_2") (pintype "passive"))
      (node (ref "C689") (pin "2") (pinfunction "2_2") (pintype "passive"))
      (node (ref "C690") (pin "2") (pinfunction "2_2") (pintype "passive"))
      (node (ref "U1") (pin "H14") (pinfunction "VDDARM_IN_1_H14") (pintype "passive"))
      (node (ref "U1") (pin "J14") (pinfunction "VDDARM_IN_2_J14") (pintype "passive"))
      (node (ref "U1") (pin "K14") (pinfunction "VDDARM_IN_3_K14") (pintype "passive"))
      (node (ref "U1") (pin "K9") (pinfunction "VDDARM_IN_9_K9") (pintype "passive"))
      (node (ref "U1") (pin "L14") (pinfunction "VDDARM_IN_4_L14") (pintype "passive"))
      (node (ref "U1") (pin "L9") (pinfunction "VDDARM_IN_10_L9") (pintype "passive"))
      (node (ref "U1") (pin "M14") (pinfunction "VDDARM_IN_5_M14") (pintype "passive"))
      (node (ref "U1") (pin "M9") (pinfunction "VDDARM_IN_11_M9") (pintype "passive"))
      (node (ref "U1") (pin "N14") (pinfunction "VDDARM_IN_6_N14") (pintype "passive"))
      (node (ref "U1") (pin "N9") (pinfunction "VDDARM_IN_12_N9") (pintype "passive"))
      (node (ref "U1") (pin "P14") (pinfunction "VDDARM_IN_7_P14") (pintype "passive"))
      (node (ref "U1") (pin "P9") (pinfunction "VDDARM_IN_13_P9") (pintype "passive"))
      (node (ref "U1") (pin "R14") (pinfunction "VDDARM_IN_8_R14") (pintype "passive"))
      (node (ref "U1") (pin "R9") (pinfunction "VDDARM_IN_14_R9") (pintype "passive"))
      (node (ref "U1") (pin "T9") (pinfunction "VDDARM_IN_15_T9") (pintype "passive"))
      (node (ref "U1") (pin "U9") (pinfunction "VDDARM_IN_16_U9") (pintype "passive"))
    )
    (net (code "13") (name "VDDHIGH_IN") (class "Default")
      (node (ref "C623") (pin "2") (pinfunction "2_2") (pintype "passive"))
      (node (ref "C652") (pin "2") (pinfunction "2_2") (pintype "passive"))
      (node (ref "D10") (pin "1") (pinfunction "A_1") (pintype "passive"))
      (node (ref "SH1") (pin "1") (pinfunction "VCCIO_1") (pintype "passive"))
      (node (ref "SH1") (pin "2") (pinfunction "VCCIO_2") (pintype "passive"))
      (node (ref "U1") (pin "H9") (pinfunction "VDDHIGH_IN_1_H9") (pintype "passive"))
      (node (ref "U1") (pin "J9") (pinfunction "VDDHIGH_IN_2_J9") (pintype "passive"))
    )
    (net (code "14") (name "VDDPU") (class "Default")
      (node (ref "C710") (pin "2") (pinfunction "2_2") (pintype "passive"))
      (node (ref "C711") (pin "2") (pinfunction "2_2") (pintype "passive"))
      (node (ref "C712") (pin "2") (pinfunction "2_2") (pintype "passive"))
      (node (ref "C713") (pin "2") (pinfunction "2_2") (pintype "passive"))
      (node (ref "C714") (pin "2") (pinfunction "2_2") (pintype "passive"))
      (node (ref "C716") (pin "2") (pinfunction "2_2") (pintype "passive"))
      (node (ref "U1") (pin "H17") (pinfunction "VDDPU_CAP_8_H17") (pintype "passive"))
      (node (ref "U1") (pin "J17") (pinfunction "VDDPU_CAP_9_J17") (pintype "passive"))
      (node (ref "U1") (pin "K17") (pinfunction "VDDPU_CAP_10_K17") (pintype "passive"))
      (node (ref "U1") (pin "L17") (pinfunction "VDDPU_CAP_11_L17") (pintype "passive"))
      (node (ref "U1") (pin "M17") (pinfunction "VDDPU_CAP_12_M17") (pintype "passive"))
      (node (ref "U1") (pin "N17") (pinfunction "VDDPU_CAP_13_N17") (pintype "passive"))
      (node (ref "U1") (pin "P17") (pinfunction "VDDPU_CAP_14_P17") (pintype "passive"))
    )
    (net (code "15") (name "VDDSOC") (class "Default")
      (node (ref "C40") (pin "2") (pinfunction "2_2") (pintype "passive"))
      (node (ref "C604") (pin "2") (pinfunction "2_2") (pintype "passive"))
      (node (ref "C694") (pin "2") (pinfunction "2_2") (pintype "passive"))
      (node (ref "C698") (pin "2") (pinfunction "2_2") (pintype "passive"))
      (node (ref "C701") (pin "2") (pinfunction "2_2") (pintype "passive"))
      (node (ref "C702") (pin "2") (pinfunction "2_2") (pintype "passive"))
      (node (ref "C703") (pin "2") (pinfunction "2_2") (pintype "passive"))
      (node (ref "C704") (pin "2") (pinfunction "2_2") (pintype "passive"))
      (node (ref "C705") (pin "2") (pinfunction "2_2") (pintype "passive"))
      (node (ref "C706") (pin "2") (pinfunction "2_2") (pintype "passive"))
      (node (ref "C707") (pin "2") (pinfunction "2_2") (pintype "passive"))
      (node (ref "U1") (pin "H16") (pinfunction "VDDSOC_IN_1_H16") (pintype "passive"))
      (node (ref "U1") (pin "J16") (pinfunction "VDDSOC_IN_2_J16") (pintype "passive"))
      (node (ref "U1") (pin "K16") (pinfunction "VDDSOC_IN_3_K16") (pintype "passive"))
      (node (ref "U1") (pin "L16") (pinfunction "VDDSOC_IN_4_L16") (pintype "passive"))
      (node (ref "U1") (pin "M16") (pinfunction "VDDSOC_IN_5_M16") (pintype "passive"))
      (node (ref "U1") (pin "N16") (pinfunction "VDDSOC_IN_6_N16") (pintype "passive"))
      (node (ref "U1") (pin "P16") (pinfunction "VDDSOC_IN_7_P16") (pintype "passive"))
      (node (ref "U1") (pin "R16") (pinfunction "VDDSOC_IN_8_R16") (pintype "passive"))
      (node (ref "U1") (pin "T16") (pinfunction "VDDSOC_IN_9_T16") (pintype "passive"))
      (node (ref "U1") (pin "U16") (pinfunction "VDDSOC_IN_10_U16") (pintype "passive"))
    )
    (net (code "16") (name "VDDSOC_CAP") (class "Default")
      (node (ref "C656") (pin "2") (pinfunction "2_2") (pintype "passive"))
      (node (ref "C661") (pin "2") (pinfunction "2_2") (pintype "passive"))
      (node (ref "C674") (pin "2") (pinfunction "2_2") (pintype "passive"))
      (node (ref "C676") (pin "2") (pinfunction "2_2") (pintype "passive"))
      (node (ref "C682") (pin "2") (pinfunction "2_2") (pintype "passive"))
      (node (ref "C691") (pin "2") (pinfunction "2_2") (pintype "passive"))
      (node (ref "C692") (pin "2") (pinfunction "2_2") (pintype "passive"))
      (node (ref "U1") (pin "R10") (pinfunction "VDDSOC_CAP_1_R10") (pintype "passive"))
      (node (ref "U1") (pin "T10") (pinfunction "VDDSOC_CAP_2_T10") (pintype "passive"))
      (node (ref "U1") (pin "T13") (pinfunction "VDDSOC_CAP_3_T13") (pintype "passive"))
      (node (ref "U1") (pin "T14") (pinfunction "VDDSOC_CAP_4_T14") (pintype "passive"))
      (node (ref "U1") (pin "U10") (pinfunction "VDDSOC_CAP_5_U10") (pintype "passive"))
      (node (ref "U1") (pin "U13") (pinfunction "VDDSOC_CAP_6_U13") (pintype "passive"))
      (node (ref "U1") (pin "U14") (pinfunction "VDDSOC_CAP_7_U14") (pintype "passive"))
    )
    (net (code "17") (name "VDD_ARM_CAP") (class "Default")
      (node (ref "C658") (pin "2") (pinfunction "2_2") (pintype "passive"))
      (node (ref "C659") (pin "2") (pinfunction "2_2") (pintype "passive"))
      (node (ref "C660") (pin "2") (pinfunction "2_2") (pintype "passive"))
      (node (ref "C663") (pin "2") (pinfunction "2_2") (pintype "passive"))
      (node (ref "C669") (pin "2") (pinfunction "2_2") (pintype "passive"))
      (node (ref "C670") (pin "2") (pinfunction "2_2") (pintype "passive"))
      (node (ref "C671") (pin "2") (pinfunction "2_2") (pintype "passive"))
      (node (ref "C672") (pin "2") (pinfunction "2_2") (pintype "passive"))
      (node (ref "C677") (pin "2") (pinfunction "2_2") (pintype "passive"))
      (node (ref "C679") (pin "2") (pinfunction "2_2") (pintype "passive"))
      (node (ref "U1") (pin "H11") (pinfunction "VDDARM_CAP_9_H11") (pintype "passive"))
      (node (ref "U1") (pin "H13") (pinfunction "VDDARM_CAP_1_H13") (pintype "passive"))
      (node (ref "U1") (pin "J11") (pinfunction "VDDARM_CAP_10_J11") (pintype "passive"))
      (node (ref "U1") (pin "J13") (pinfunction "VDDARM_CAP_2_J13") (pintype "passive"))
      (node (ref "U1") (pin "K11") (pinfunction "VDDARM_CAP_11_K11") (pintype "passive"))
      (node (ref "U1") (pin "K13") (pinfunction "VDDARM_CAP_3_K13") (pintype "passive"))
      (node (ref "U1") (pin "L11") (pinfunction "VDDARM_CAP_12_L11") (pintype "passive"))
      (node (ref "U1") (pin "L13") (pinfunction "VDDARM_CAP_4_L13") (pintype "passive"))
      (node (ref "U1") (pin "M11") (pinfunction "VDDARM_CAP_13_M11") (pintype "passive"))
      (node (ref "U1") (pin "M13") (pinfunction "VDDARM_CAP_5_M13") (pintype "passive"))
      (node (ref "U1") (pin "N11") (pinfunction "VDDARM_CAP_14_N11") (pintype "passive"))
      (node (ref "U1") (pin "N13") (pinfunction "VDDARM_CAP_6_N13") (pintype "passive"))
      (node (ref "U1") (pin "P11") (pinfunction "VDDARM_CAP_15_P11") (pintype "passive"))
      (node (ref "U1") (pin "P13") (pinfunction "VDDARM_CAP_7_P13") (pintype "passive"))
      (node (ref "U1") (pin "R11") (pinfunction "VDDARM_CAP_16_R11") (pintype "passive"))
      (node (ref "U1") (pin "R13") (pinfunction "VDDARM_CAP_8_R13") (pintype "passive"))
    )
    (net (code "18") (name "VDD_SNVS_CAP") (class "Default")
      (node (ref "C634") (pin "1") (pinfunction "1_1") (pintype "passive"))
      (node (ref "U1") (pin "G9") (pinfunction "VDD_SNVS_CAP_G9") (pintype "passive"))
    )
    (net (code "19") (name "VGEN3_2V5") (class "Default")
      (node (ref "R85") (pin "2") (pinfunction "2_2") (pintype "passive"))
    )
    (net (code "20") (name "VSNVS_3V0") (class "Default")
      (node (ref "C657") (pin "2") (pinfunction "2_2") (pintype "passive"))
      (node (ref "D10") (pin "2") (pinfunction "C_2") (pintype "passive"))
      (node (ref "U1") (pin "G11") (pinfunction "VDD_SNVS_IN_G11") (pintype "passive"))
    )
    (net (code "21") (name "unconnected-(U1A-GPANAIO-PadC8)") (class "Default")
      (node (ref "U1") (pin "C8") (pinfunction "GPANAIO_C8") (pintype "passive"))
    )
    (net (code "22") (name "unconnected-(U1A-NVCC_ENET-PadR19)") (class "Default")
      (node (ref "U1") (pin "R19") (pinfunction "NVCC_ENET_R19") (pintype "passive"))
    )
  )
)
